# 5v_LP_Test_Control.net
KiCad netlist of a schematic drawn in EAGLE
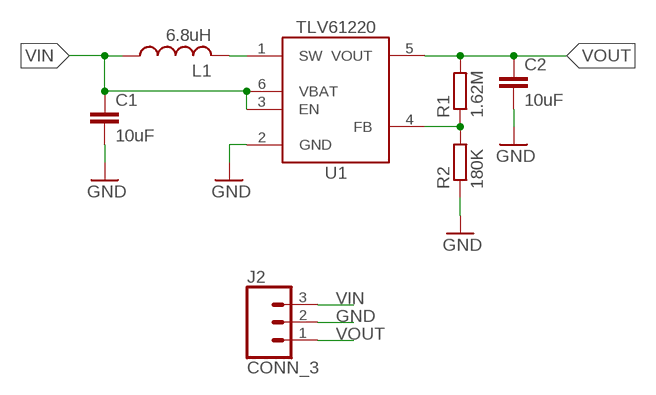
[diagram p0: schematic, sheet 1]

(export (version "E")
  (design (tool "Eeschema 10.0.6"))
  (components
    (comp (ref "C1")
      (value "10uF")
      (footprint "eagle-import:C0805")
      (fields (field (name "MF") "Murata") (field (name "MPN") "GRM21BR61C106KE15K"))
      (libsource (lib "eagle-import") (part "C-EUC080510UF"))
    )
    (comp (ref "C2")
      (value "10uF")
      (footprint "eagle-import:C0805")
      (fields (field (name "MF") "Murata") (field (name "MPN") "GRM21BR61C106KE15K"))
      (libsource (lib "eagle-import") (part "C-EUC080510UF"))
    )
    (comp (ref "J2")
      (value "CONN_3")
      (footprint "eagle-import:1X03")
      (libsource (lib "eagle-import") (part "CONN_3"))
    )
    (comp (ref "L1")
      (value "6.8uH")
      (footprint "eagle-import:1008")
      (libsource (lib "eagle-import") (part "INDUCTOR1008"))
    )
    (comp (ref "R1")
      (value "1.62M")
      (footprint "eagle-import:R0603")
      (fields (field (name "MF") "Yageo"))
      (libsource (lib "eagle-import") (part "R-EU_R0603"))
    )
    (comp (ref "R2")
      (value "180K")
      (footprint "eagle-import:R0603")
      (fields (field (name "MF") "Yageo"))
      (libsource (lib "eagle-import") (part "R-EU_R0603"))
    )
    (comp (ref "U1")
      (value "TLV61220DBV")
      (footprint "eagle-import:DBV_R-PDSO-G6")
      (fields (field (name "MF") "TI") (field (name "MPN") "TLV61220DBVR"))
      (libsource (lib "eagle-import") (part "TLV61220DBV"))
    )
  )
  (nets
    (net (code "1") (name "GND") (class "Default")
      (node (ref "C1") (pin "2") (pinfunction "2_2") (pintype "passive"))
      (node (ref "C2") (pin "2") (pinfunction "2_2") (pintype "passive"))
      (node (ref "J2") (pin "2") (pinfunction "2_2") (pintype "passive"))
      (node (ref "R2") (pin "1") (pinfunction "1_1") (pintype "passive"))
      (node (ref "U1") (pin "2") (pinfunction "GND_2") (pintype "power_in"))
    )
    (net (code "2") (name "Net-(U1-FB)") (class "Default")
      (node (ref "R1") (pin "1") (pinfunction "1_1") (pintype "passive"))
      (node (ref "R2") (pin "2") (pinfunction "2_2") (pintype "passive"))
      (node (ref "U1") (pin "4") (pinfunction "FB_4") (pintype "input"))
    )
    (net (code "3") (name "Net-(U1-SW)") (class "Default")
      (node (ref "L1") (pin "2") (pinfunction "2_2") (pintype "passive"))
      (node (ref "U1") (pin "1") (pinfunction "SW_1") (pintype "power_in"))
    )
    (net (code "4") (name "VIN") (class "Default")
      (node (ref "C1") (pin "1") (pinfunction "1_1") (pintype "passive"))
      (node (ref "J2") (pin "3") (pinfunction "3_3") (pintype "passive"))
      (node (ref "L1") (pin "1") (pinfunction "1_1") (pintype "passive"))
      (node (ref "U1") (pin "3") (pinfunction "EN_3") (pintype "input"))
      (node (ref "U1") (pin "6") (pinfunction "VBAT_6") (pintype "power_in"))
    )
    (net (code "5") (name "VOUT") (class "Default")
      (node (ref "C2") (pin "1") (pinfunction "1_1") (pintype "passive"))
      (node (ref "J2") (pin "1") (pinfunction "1_1") (pintype "passive"))
      (node (ref "R1") (pin "2") (pinfunction "2_2") (pintype "passive"))
      (node (ref "U1") (pin "5") (pinfunction "VOUT_5") (pintype "power_in"))
    )
  )
)
